# H0FR70.net
KiCad netlist of a schematic drawn in EAGLE
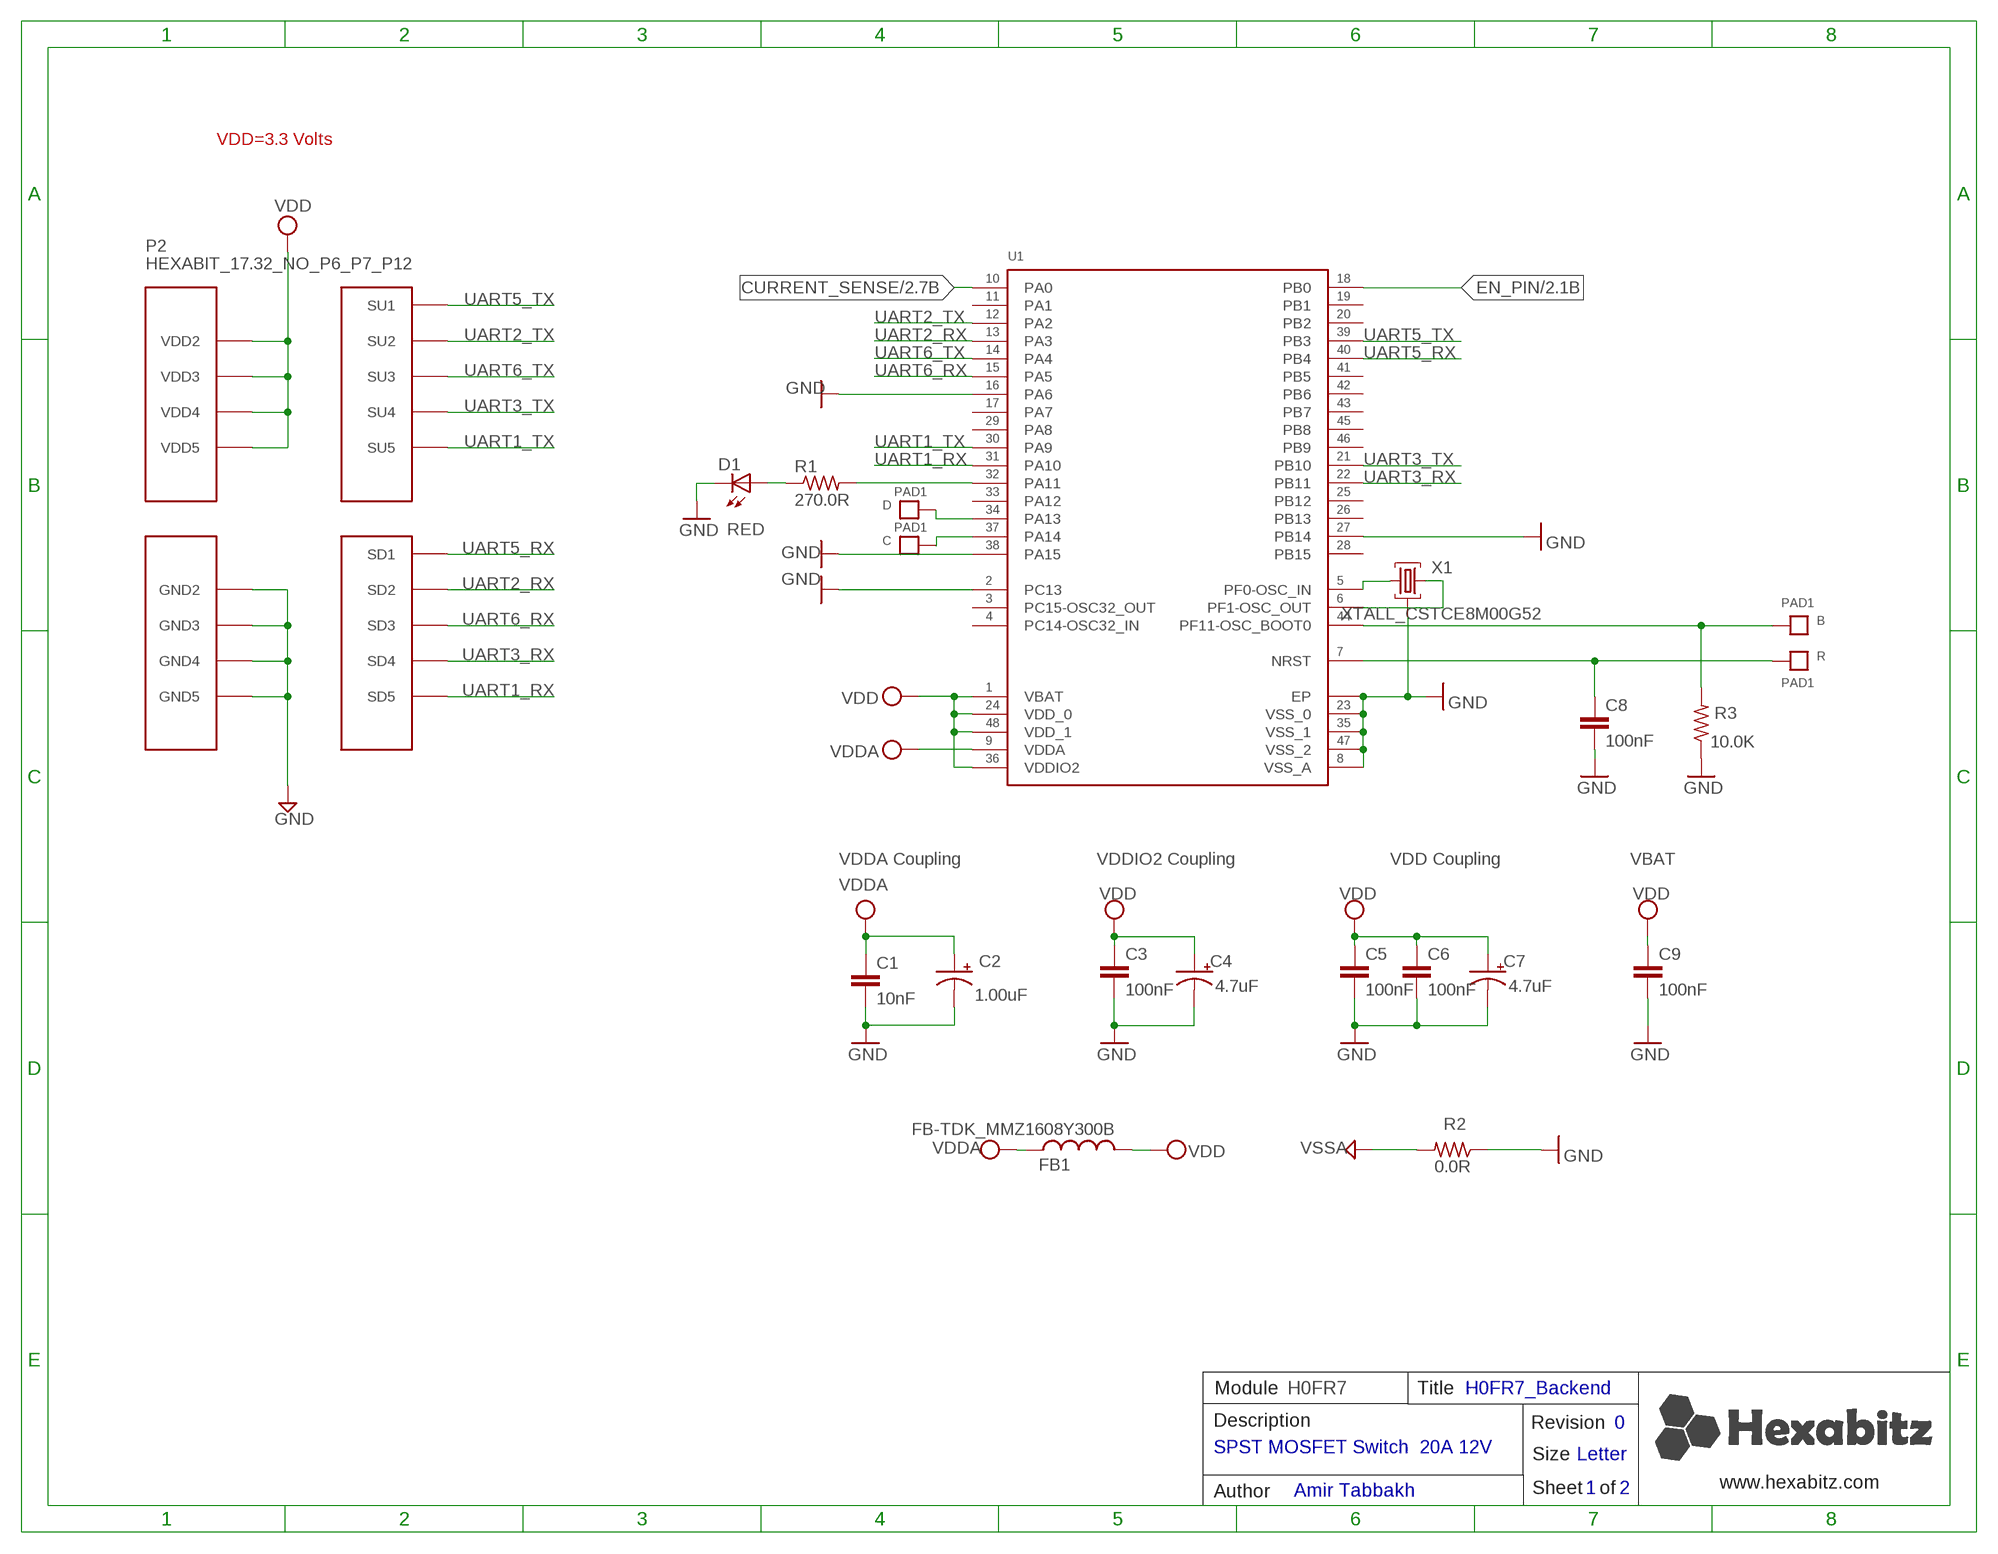
[diagram p0: schematic, sheet 1]
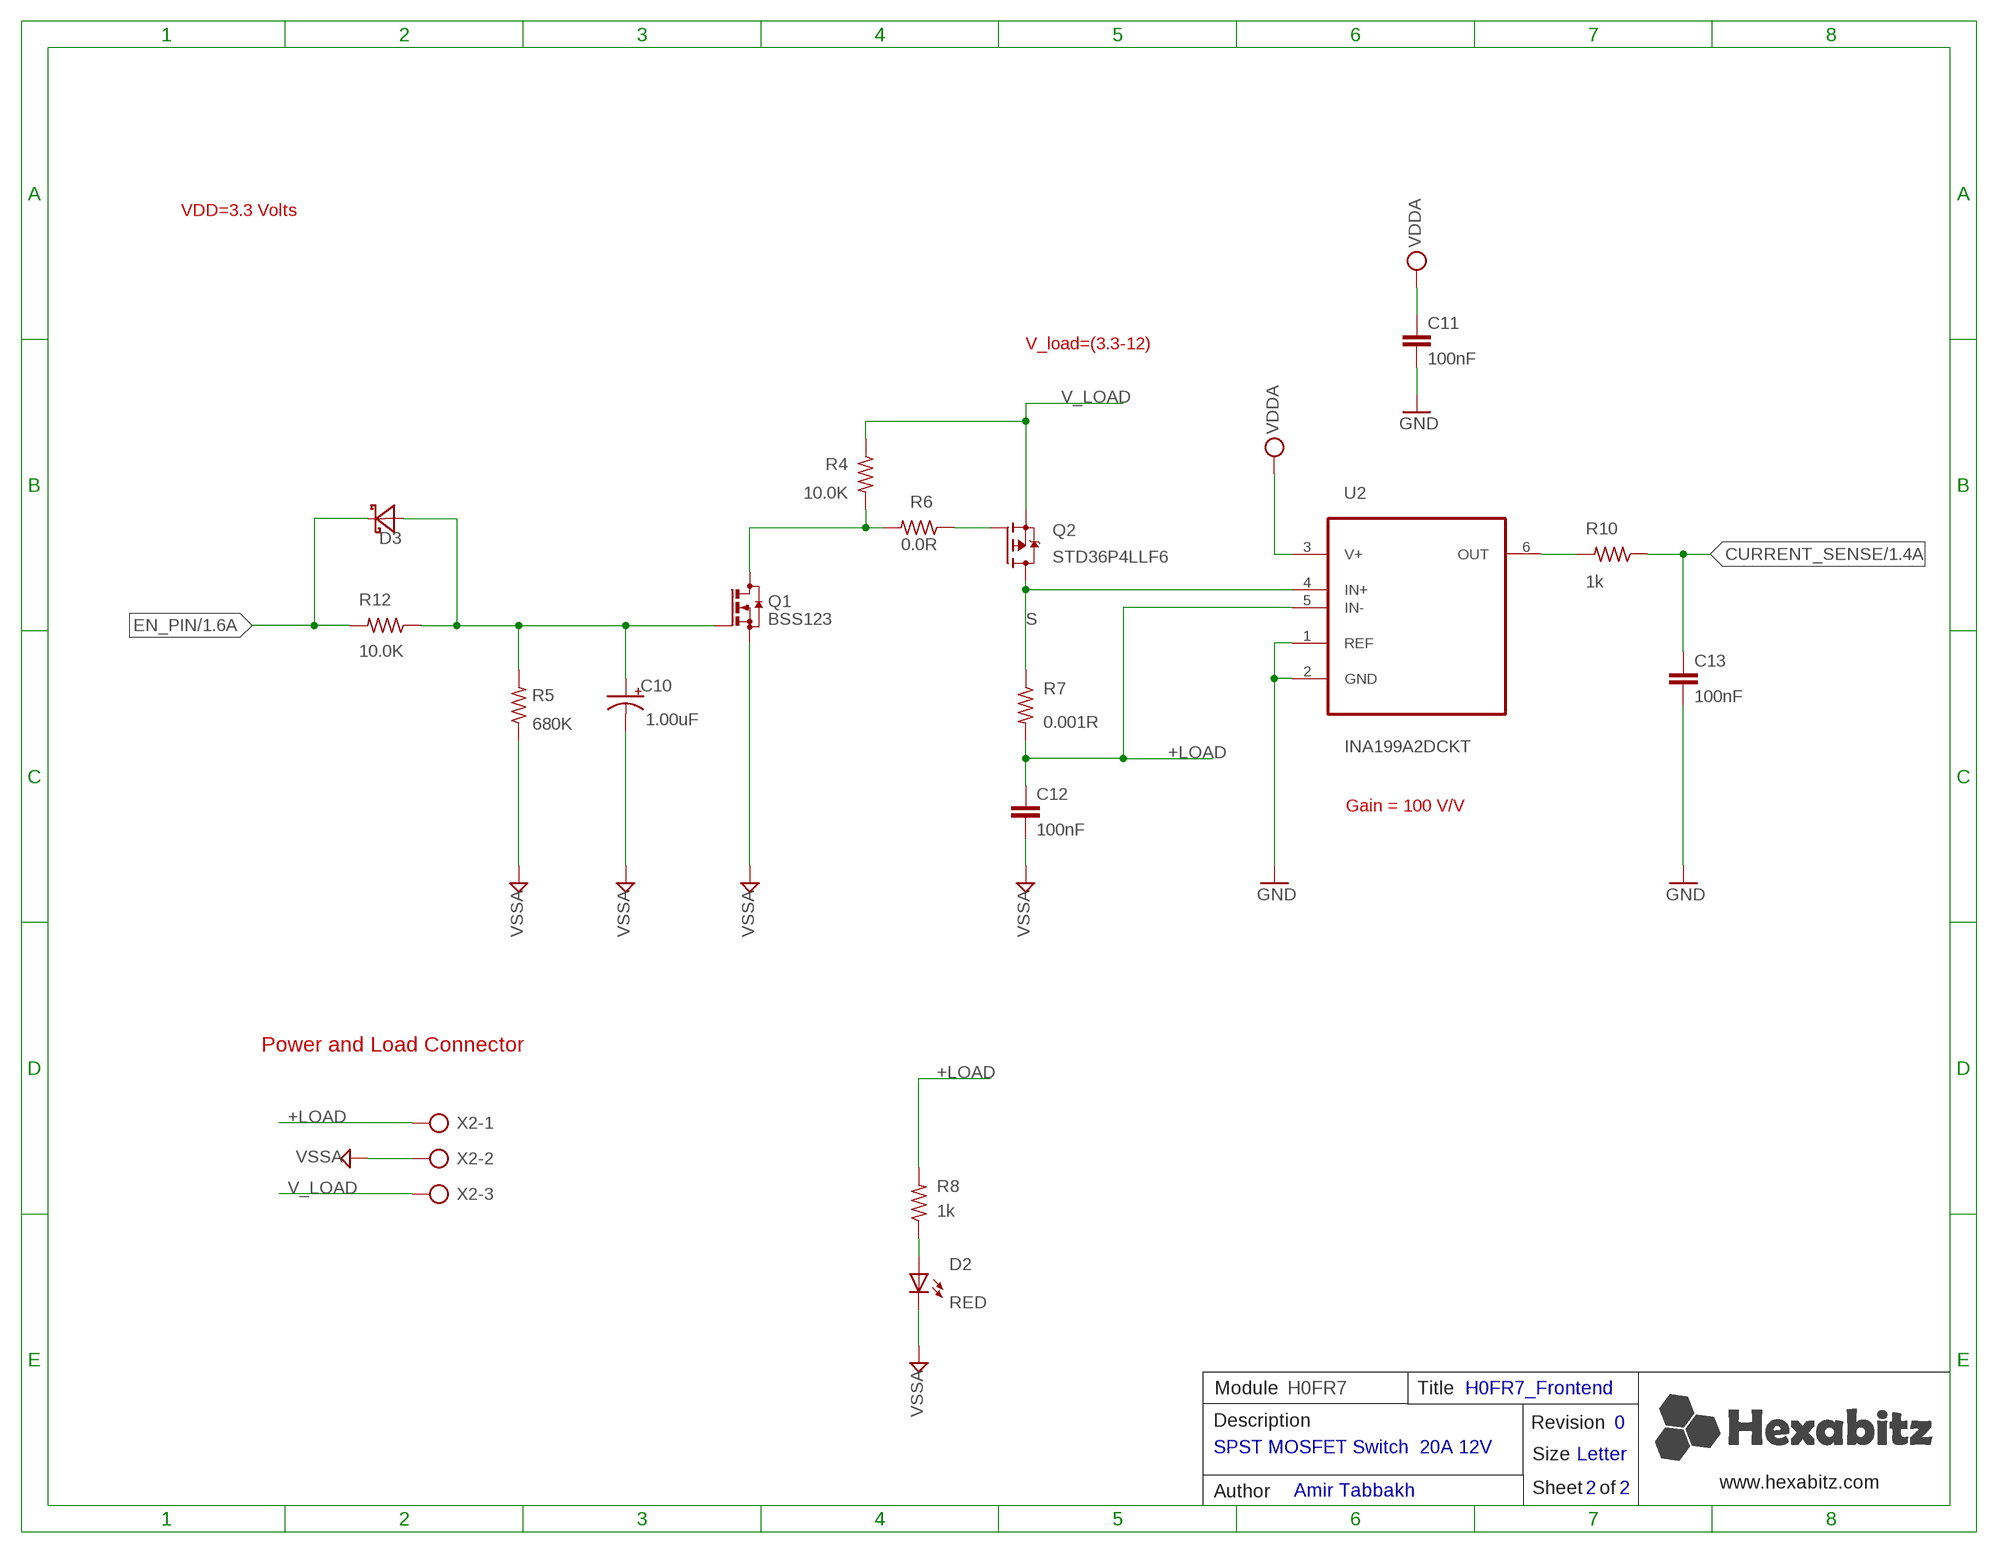
[diagram p1: schematic, sheet 2]

(export (version "E")
  (design (tool "Eeschema 10.0.6"))
  (components
    (comp (ref "B")
      (value "PAD1")
      (footprint "eagle-import:PAD1")
      (libsource (lib "eagle-import") (part "PAD1"))
    )
    (comp (ref "C")
      (value "PAD1")
      (footprint "eagle-import:PAD1")
      (libsource (lib "eagle-import") (part "PAD1"))
    )
    (comp (ref "C1")
      (value "10nF")
      (footprint "eagle-import:C-0603")
      (fields
        (field (name "CAPACITANCE") "10nF")
        (field (name "MFN") "KEMET")
        (field (name "MPN") "C0603C103K5RACTU")
        (field (name "OCTOPART_URL") "https://octopart.com/c0603c103k5ractu-kemet-133094?r=sp&s=R_iPBxLnSmGqhkU2rIMFpg")
        (field (name "TOLERANCE") "10%")
        (field (name "VOLTAGE_RATING") "50V")
      )
      (libsource (lib "eagle-import") (part "C-0603"))
    )
    (comp (ref "C2")
      (value "1.00uF")
      (footprint "eagle-import:C-0805-POL")
      (fields
        (field (name "CAPACITANCE") "1.00uF")
        (field (name "MFN") "Yageo")
        (field (name "MPN") "CC0805KKX7R7BB105")
        (field (name "OCTOPART_URL") "https://octopart.com/cc0805kkx7r7bb105-yageo-8376555?r=sp&s=YKl1wwtkROau_X5nniH2ig")
        (field (name "TOLERANCE") "10%")
        (field (name "VOLTAGE_RATING") "16V")
      )
      (libsource (lib "eagle-import") (part "C-0805-POL"))
    )
    (comp (ref "C3")
      (value "100nF")
      (footprint "eagle-import:C-0603")
      (fields
        (field (name "CAPACITANCE") "100nF")
        (field (name "MFN") "KEMET")
        (field (name "MPN") "C0603C104K8RACTU")
        (field (name "OCTOPART_URL") "https://octopart.com/c0603c104k8ractu-kemet-145075?r=sp&s=9bS9ASSwSEqMCE9KBEQZ0g")
        (field (name "TOLERANCE") "10%")
        (field (name "VOLTAGE_RATING") "10V")
      )
      (libsource (lib "eagle-import") (part "C-0603"))
    )
    (comp (ref "C4")
      (value "4.7uF")
      (footprint "eagle-import:C-0805-POL")
      (fields
        (field (name "CAPACITANCE") "4.7uF")
        (field (name "MFN") "Murata")
        (field (name "MPN") "GRM21BC81E475KA12L")
        (field (name "OCTOPART_URL") "https://octopart.com/grm21bc81e475ka12l-murata-10331911?r=sp&s=RY3qZSD8T6mG6TC9CHI5qQ")
        (field (name "TOLERANCE") "10%")
        (field (name "VOLTAGE_RATING") "25V")
      )
      (libsource (lib "eagle-import") (part "C-0805-POL"))
    )
    (comp (ref "C5")
      (value "100nF")
      (footprint "eagle-import:C-0603")
      (fields
        (field (name "CAPACITANCE") "100nF")
        (field (name "MFN") "KEMET")
        (field (name "MPN") "C0603C104K8RACTU")
        (field (name "OCTOPART_URL") "https://octopart.com/c0603c104k8ractu-kemet-145075?r=sp&s=9bS9ASSwSEqMCE9KBEQZ0g")
        (field (name "TOLERANCE") "10%")
        (field (name "VOLTAGE_RATING") "10")
      )
      (libsource (lib "eagle-import") (part "C-0603"))
    )
    (comp (ref "C6")
      (value "100nF")
      (footprint "eagle-import:C-0603")
      (fields
        (field (name "CAPACITANCE") "100nF")
        (field (name "MFN") "KEMET")
        (field (name "MPN") "C0603C104K8RACTU")
        (field (name "OCTOPART_URL") "https://octopart.com/c0603c104k8ractu-kemet-145075?r=sp&s=9bS9ASSwSEqMCE9KBEQZ0g")
        (field (name "TOLERANCE") "10%")
        (field (name "VOLTAGE_RATING") "10V")
      )
      (libsource (lib "eagle-import") (part "C-0603"))
    )
    (comp (ref "C7")
      (value "4.7uF")
      (footprint "eagle-import:C-0805-POL")
      (fields
        (field (name "CAPACITANCE") "4.7uF")
        (field (name "MFN") "Murata")
        (field (name "MPN") "GRM21BC81E475KA12L")
        (field (name "OCTOPART_URL") "https://octopart.com/grm21bc81e475ka12l-murata-10331911?r=sp&s=RY3qZSD8T6mG6TC9CHI5qQ")
        (field (name "TOLERANCE") "10%")
        (field (name "VOLTAGE_RATING") "25V")
      )
      (libsource (lib "eagle-import") (part "C-0805-POL"))
    )
    (comp (ref "C8")
      (value "100nF")
      (footprint "eagle-import:C-0603")
      (fields
        (field (name "CAPACITANCE") "100nF")
        (field (name "MFN") "KEMET")
        (field (name "MPN") "C0603C104K8RACTU")
        (field (name "OCTOPART_URL") "https://octopart.com/c0603c104k8ractu-kemet-145075?r=sp&s=9bS9ASSwSEqMCE9KBEQZ0g")
        (field (name "TOLERANCE") "10%")
        (field (name "VOLTAGE_RATING") "10V")
      )
      (libsource (lib "eagle-import") (part "C-0603"))
    )
    (comp (ref "C9")
      (value "100nF")
      (footprint "eagle-import:C-0603")
      (fields
        (field (name "CAPACITANCE") "100nF")
        (field (name "MFN") "KEMET")
        (field (name "MPN") "C0603C104K8RACTU")
        (field (name "OCTOPART_URL") "https://octopart.com/c0603c104k8ractu-kemet-145075?r=sp&s=9bS9ASSwSEqMCE9KBEQZ0g")
        (field (name "TOLERANCE") "10V")
        (field (name "VOLTAGE_RATING") "10%")
      )
      (libsource (lib "eagle-import") (part "C-0603"))
    )
    (comp (ref "D")
      (value "PAD1")
      (footprint "eagle-import:PAD1")
      (libsource (lib "eagle-import") (part "PAD1"))
    )
    (comp (ref "D1")
      (value "RED")
      (footprint "eagle-import:VLMS1300-GS08")
      (fields
        (field (name "MPN") "VLMS1300-GS08")
        (field (name "MFN") "Vishay")
        (field (name "MPN_1") "VLMS1300-GS08")
        (field (name "OCTOPART_URL") "https://octopart.com/vlms1300-gs08-vishay-21709201?r=sp&s=_gcP4_q8T1SC6PJQPTQ9yA")
      )
      (libsource (lib "eagle-import") (part "VLMS1300-GS08"))
    )
    (comp (ref "FB1")
      (value "FB-TDK_MMZ1608Y300B")
      (footprint "eagle-import:FB-TDK_MMZ1608Y300B")
      (fields
        (field (name "MFN") "TDK ")
        (field (name "MPN") "MMZ1608Y300B")
        (field (name "OCTOPART_URL") "https://octopart.com/mmz1608y300b-tdk-368280?r=sp&s=cd9_2ZEqQ9q9UNBuQgHAiA")
      )
      (libsource (lib "eagle-import") (part "FB-TDK_MMZ1608Y300B"))
    )
    (comp (ref "P2")
      (value "HEXABIT_17.32_NO_P6_P7_P12")
      (footprint "eagle-import:HEXABIT_17.32_NO_P6_P7_P12")
      (libsource (lib "eagle-import") (part "HEXABIT_?_NO_P6_P7_P1217.32"))
    )
    (comp (ref "R")
      (value "PAD1")
      (footprint "eagle-import:PAD1")
      (libsource (lib "eagle-import") (part "PAD1"))
    )
    (comp (ref "R1")
      (value "270.0R")
      (footprint "eagle-import:R-0603")
      (fields
        (field (name "MFN") "Yageo")
        (field (name "MPN") "RC0603FR-07270RL")
        (field (name "OCTOPART_URL") "https://octopart.com/search?q=RC0603FR-07270RL&start=0")
        (field (name "RESISTANCE") "270.0 Ohm")
        (field (name "TOLERANCE") "1%")
      )
      (libsource (lib "eagle-import") (part "R-0603"))
    )
    (comp (ref "R2")
      (value "0.0R")
      (footprint "eagle-import:R-0603")
      (fields
        (field (name "MFN") "Yageo")
        (field (name "MPN") "RC0603JR-070RL")
        (field (name "OCTOPART_URL") "https://octopart.com/rc0603jr-070rl-yageo-1241539?r=sp&s=X2NteqRjRNWrnx42Y0aliA")
        (field (name "RESISTANCE") "0.0 Ohm")
      )
      (libsource (lib "eagle-import") (part "R-0603"))
    )
    (comp (ref "R3")
      (value "10.0K")
      (footprint "eagle-import:R-0603")
      (fields
        (field (name "MFN") "Yageo")
        (field (name "MPN") "RC0603JR-0710KL")
        (field (name "OCTOPART_URL") "https://octopart.com/search?q=RC0603JR-0710KL&start=0")
        (field (name "RESISTANCE") "10.0K Ohm")
        (field (name "TOLERANCE") "5%")
      )
      (libsource (lib "eagle-import") (part "R-0603"))
    )
    (comp (ref "U1")
      (value "STM32F091CBU6")
      (footprint "eagle-import:STM32F091CBU6")
      (libsource (lib "eagle-import") (part "STM32F091CBU6"))
    )
    (comp (ref "X1")
      (value "XTALL_CSTCE8M00G52")
      (footprint "eagle-import:XTALL_CSTCE8M00G52")
      (fields (field (name "MPN") "CSTCE8M00G52Z-R0"))
      (libsource (lib "eagle-import") (part "XTALL_CSTCE8M00G52"))
    )
    (comp (ref "C10")
      (value "1.00uF")
      (footprint "eagle-import:C-0805-POL")
      (fields
        (field (name "CAPACITANCE") "1.00uF")
        (field (name "MFN") "Yageo")
        (field (name "MPN") "CC0805KKX7R7BB105")
        (field (name "OCTOPART_URL") "https://octopart.com/cc0805kkx7r7bb105-yageo-8376555?r=sp&s=YKl1wwtkROau_X5nniH2ig")
        (field (name "TOLERANCE") "10%")
        (field (name "VOLTAGE_RATING") "16V")
      )
      (libsource (lib "eagle-import") (part "C-0805-POL"))
    )
    (comp (ref "C11")
      (value "100nF")
      (footprint "eagle-import:C-0603")
      (fields
        (field (name "CAPACITANCE") "100nF")
        (field (name "MFN") "KEMET")
        (field (name "MPN") "C0603C104K8RACTU")
        (field (name "OCTOPART_URL") "https://octopart.com/c0603c104k8ractu-kemet-145075?r=sp&s=9bS9ASSwSEqMCE9KBEQZ0g")
        (field (name "TOLERANCE") "10V")
        (field (name "VOLTAGE_RATING") "10%")
      )
      (libsource (lib "eagle-import") (part "C-0603"))
    )
    (comp (ref "C12")
      (value "100nF")
      (footprint "eagle-import:C-0603")
      (fields
        (field (name "CAPACITANCE") "100nF")
        (field (name "MFN") "KEMET")
        (field (name "MPN") "C0603C104K8RACTU")
        (field (name "OCTOPART_URL") "https://octopart.com/c0603c104k8ractu-kemet-145075?r=sp&s=9bS9ASSwSEqMCE9KBEQZ0g")
        (field (name "TOLERANCE") "10%")
        (field (name "VOLTAGE_RATING") "10V")
      )
      (libsource (lib "eagle-import") (part "C-0603"))
    )
    (comp (ref "C13")
      (value "100nF")
      (footprint "eagle-import:C-0603")
      (fields
        (field (name "CAPACITANCE") "100nF")
        (field (name "MFN") "KEMET")
        (field (name "MPN") "C0603C104K8RACTU")
        (field (name "OCTOPART_URL") "https://octopart.com/c0603c104k8ractu-kemet-145075?r=sp&s=9bS9ASSwSEqMCE9KBEQZ0g")
        (field (name "TOLERANCE") "10%")
        (field (name "VOLTAGE_RATING") "10V")
      )
      (libsource (lib "eagle-import") (part "C-0603"))
    )
    (comp (ref "D2")
      (value "RED")
      (footprint "eagle-import:VLMS1300-GS08")
      (fields
        (field (name "MPN") "VLMS1300-GS08")
        (field (name "MFN") "Vishay")
        (field (name "MPN_1") "VLMO1300-GS08 ")
        (field (name "OCTOPART_URL") "https://octopart.com/vlmo1300-gs08-vishay-21709200?r=sp#")
      )
      (libsource (lib "eagle-import") (part "VLMS1300-GS08"))
    )
    (comp (ref "D3")
      (value "SMD-DIODE-SCHOTTKY-40V-300MA(SOD-323)")
      (footprint "eagle-import:SOD-323")
      (fields (field (name "MF") "STMicroelectronics") (field (name "MP") "BAT54JFILM"))
      (libsource (lib "eagle-import") (part "SMD-DIODE-SCHOTTKY-40V-300MA(SOD-323)"))
    )
    (comp (ref "Q1")
      (value "BSS123")
      (footprint "eagle-import:SOT23")
      (libsource (lib "eagle-import") (part "BSS123"))
    )
    (comp (ref "Q2")
      (value "STD36P4LLF6")
      (footprint "eagle-import:DPAK-3")
      (libsource (lib "eagle-import") (part "STD36P4LLF6"))
    )
    (comp (ref "R4")
      (value "10.0K")
      (footprint "eagle-import:R-0603")
      (fields
        (field (name "MFN") "Yageo")
        (field (name "MPN") "RC0603JR-0710KL")
        (field (name "OCTOPART_URL") "https://octopart.com/search?q=RC0603JR-0710KL&start=0")
        (field (name "RESISTANCE") "10.0K Ohm")
        (field (name "TOLERANCE") "5%")
      )
      (libsource (lib "eagle-import") (part "R-0603"))
    )
    (comp (ref "R5")
      (value "680K")
      (footprint "eagle-import:R-0603")
      (fields
        (field (name "MFN") "Yageo")
        (field (name "MPN") "RC0603JR-07680KL")
        (field (name "OCTOPART_URL") "https://octopart.com/rc0603jr-07680kl-yageo-40953169?r=sp")
        (field (name "RESISTANCE") "680K Ohm")
        (field (name "TOLERANCE") "5%")
      )
      (libsource (lib "eagle-import") (part "R-0603"))
    )
    (comp (ref "R6")
      (value "0.0R")
      (footprint "eagle-import:R-0603")
      (fields
        (field (name "MFN") "Yageo")
        (field (name "MPN") "RC0603JR-070RL")
        (field (name "OCTOPART_URL") "https://octopart.com/rc0603jr-070rl-yageo-1241539?r=sp&s=X2NteqRjRNWrnx42Y0aliA")
        (field (name "RESISTANCE") "0.0 Ohm")
      )
      (libsource (lib "eagle-import") (part "R-0603"))
    )
    (comp (ref "R7")
      (value "0.001R")
      (footprint "eagle-import:R2512")
      (libsource (lib "eagle-import") (part "R-US_R2512"))
    )
    (comp (ref "R8")
      (value "1k")
      (footprint "eagle-import:R-0603")
      (fields
        (field (name "MFN") "Yageo")
        (field (name "MPN") "RC0603JR-071KL")
        (field (name "OCTOPART_URL") "https://octopart.com/rc0603jr-071kl-yageo-55402888?r=sp")
        (field (name "RESISTANCE") "1k")
        (field (name "TOLERANCE") "1%")
      )
      (libsource (lib "eagle-import") (part "R-0603"))
    )
    (comp (ref "R10")
      (value "1k")
      (footprint "eagle-import:R-0603")
      (fields
        (field (name "MFN") "Yageo")
        (field (name "MPN") "RC0603JR-071KL")
        (field (name "OCTOPART_URL") "https://octopart.com/rc0603jr-071kl-yageo-55402888?r=sp")
        (field (name "RESISTANCE") "1k")
        (field (name "TOLERANCE") "5%")
      )
      (libsource (lib "eagle-import") (part "R-0603"))
    )
    (comp (ref "R12")
      (value "10.0K")
      (footprint "eagle-import:R-0603")
      (fields
        (field (name "MFN") "Yageo")
        (field (name "MPN") "RC0603JR-0710KL")
        (field (name "OCTOPART_URL") "https://octopart.com/search?q=RC0603JR-0710KL&start=0")
        (field (name "RESISTANCE") "10.0K Ohm")
        (field (name "TOLERANCE") "5%")
      )
      (libsource (lib "eagle-import") (part "R-0603"))
    )
    (comp (ref "U2")
      (value "INA199A2DCKT")
      (footprint "eagle-import:SOT65P210X110-6N")
      (libsource (lib "eagle-import") (part "INA199A2DCKT"))
    )
    (comp (ref "X2")
      (value "AK500/3")
      (footprint "eagle-import:AK500_3")
      (libsource (lib "eagle-import") (part "AK500/3"))
    )
  )
  (nets
    (net (code "1") (name "+LOAD") (class "Default")
      (node (ref "C12") (pin "1") (pinfunction "1_1") (pintype "passive"))
      (node (ref "R7") (pin "2") (pinfunction "2_2") (pintype "passive"))
      (node (ref "R8") (pin "2") (pinfunction "2_2") (pintype "passive"))
      (node (ref "U2") (pin "5") (pinfunction "IN-_5") (pintype "input"))
      (node (ref "X2") (pin "1") (pinfunction "KL_1") (pintype "passive"))
    )
    (net (code "2") (name "AGND") (class "Default")
      (node (ref "C10") (pin "2") (pinfunction "-_2") (pintype "passive"))
      (node (ref "C12") (pin "2") (pinfunction "2_2") (pintype "passive"))
      (node (ref "D2") (pin "C") (pinfunction "C_C") (pintype "passive"))
      (node (ref "Q1") (pin "2") (pinfunction "S_2") (pintype "passive"))
      (node (ref "R2") (pin "2") (pinfunction "2_2") (pintype "passive"))
      (node (ref "R5") (pin "1") (pinfunction "1_1") (pintype "passive"))
      (node (ref "X2") (pin "2") (pinfunction "KL_2") (pintype "passive"))
    )
    (net (code "3") (name "CURRENT_SENSE") (class "Default")
      (node (ref "C13") (pin "1") (pinfunction "1_1") (pintype "passive"))
      (node (ref "R10") (pin "1") (pinfunction "1_1") (pintype "passive"))
      (node (ref "U1") (pin "P$10") (pinfunction "PA0_P$10") (pintype "bidirectional"))
    )
    (net (code "4") (name "EN_PIN") (class "Default")
      (node (ref "D3") (pin "-") (pinfunction "C_-") (pintype "passive"))
      (node (ref "R12") (pin "2") (pinfunction "2_2") (pintype "passive"))
      (node (ref "U1") (pin "P$18") (pinfunction "PB0_P$18") (pintype "bidirectional"))
    )
    (net (code "5") (name "GND") (class "Default")
      (node (ref "C1") (pin "2") (pinfunction "2_2") (pintype "passive"))
      (node (ref "C11") (pin "2") (pinfunction "2_2") (pintype "passive"))
      (node (ref "C13") (pin "2") (pinfunction "2_2") (pintype "passive"))
      (node (ref "C2") (pin "2") (pinfunction "-_2") (pintype "passive"))
      (node (ref "C3") (pin "2") (pinfunction "2_2") (pintype "passive"))
      (node (ref "C4") (pin "2") (pinfunction "-_2") (pintype "passive"))
      (node (ref "C5") (pin "2") (pinfunction "2_2") (pintype "passive"))
      (node (ref "C6") (pin "2") (pinfunction "2_2") (pintype "passive"))
      (node (ref "C7") (pin "2") (pinfunction "-_2") (pintype "passive"))
      (node (ref "C8") (pin "2") (pinfunction "2_2") (pintype "passive"))
      (node (ref "C9") (pin "2") (pinfunction "2_2") (pintype "passive"))
      (node (ref "D1") (pin "C") (pinfunction "C_C") (pintype "passive"))
      (node (ref "P2") (pin "PAD_PD10") (pinfunction "GND4_PAD_PD10") (pintype "power_in"))
      (node (ref "P2") (pin "PAD_PD11") (pinfunction "GND5_PAD_PD11") (pintype "power_in"))
      (node (ref "P2") (pin "PAD_PD8") (pinfunction "GND2_PAD_PD8") (pintype "power_in"))
      (node (ref "P2") (pin "PAD_PD9") (pinfunction "GND3_PAD_PD9") (pintype "power_in"))
      (node (ref "R2") (pin "1") (pinfunction "1_1") (pintype "passive"))
      (node (ref "R3") (pin "1") (pinfunction "1_1") (pintype "passive"))
      (node (ref "U1") (pin "EP") (pinfunction "EP_EP") (pintype "power_in"))
      (node (ref "U1") (pin "P$16") (pinfunction "PA6_P$16") (pintype "bidirectional"))
      (node (ref "U1") (pin "P$2") (pinfunction "PC13_P$2") (pintype "bidirectional"))
      (node (ref "U1") (pin "P$23") (pinfunction "VSS_0_P$23") (pintype "power_in"))
      (node (ref "U1") (pin "P$27") (pinfunction "PB14_P$27") (pintype "bidirectional"))
      (node (ref "U1") (pin "P$35") (pinfunction "VSS_1_P$35") (pintype "power_in"))
      (node (ref "U1") (pin "P$38") (pinfunction "PA15_P$38") (pintype "bidirectional"))
      (node (ref "U1") (pin "P$47") (pinfunction "VSS_2_P$47") (pintype "power_in"))
      (node (ref "U1") (pin "P$8") (pinfunction "VSS_A_P$8") (pintype "power_in"))
      (node (ref "U2") (pin "1") (pinfunction "REF_1") (pintype "input"))
      (node (ref "U2") (pin "2") (pinfunction "GND_2") (pintype "passive"))
      (node (ref "X1") (pin "P$2") (pinfunction "2_P$2") (pintype "passive"))
    )
    (net (code "6") (name "Net-(C10-+)") (class "Default")
      (node (ref "C10") (pin "1") (pinfunction "+_1") (pintype "passive"))
      (node (ref "D3") (pin "+") (pinfunction "A_+") (pintype "passive"))
      (node (ref "Q1") (pin "1") (pinfunction "G_1") (pintype "passive"))
      (node (ref "R12") (pin "1") (pinfunction "1_1") (pintype "passive"))
      (node (ref "R5") (pin "2") (pinfunction "2_2") (pintype "passive"))
    )
    (net (code "7") (name "Net-(D1-PadA)") (class "Default")
      (node (ref "D1") (pin "A") (pinfunction "A_A") (pintype "passive"))
      (node (ref "R1") (pin "1") (pinfunction "1_1") (pintype "passive"))
    )
    (net (code "8") (name "Net-(D2-PadA)") (class "Default")
      (node (ref "D2") (pin "A") (pinfunction "A_A") (pintype "passive"))
      (node (ref "R8") (pin "1") (pinfunction "1_1") (pintype "passive"))
    )
    (net (code "9") (name "Net-(Q1-D)") (class "Default")
      (node (ref "Q1") (pin "3") (pinfunction "D_3") (pintype "passive"))
      (node (ref "R4") (pin "2") (pinfunction "2_2") (pintype "passive"))
      (node (ref "R6") (pin "2") (pinfunction "2_2") (pintype "passive"))
    )
    (net (code "10") (name "Net-(Q2-G)") (class "Default")
      (node (ref "Q2") (pin "1") (pinfunction "G_1") (pintype "passive"))
      (node (ref "R6") (pin "1") (pinfunction "1_1") (pintype "passive"))
    )
    (net (code "11") (name "Net-(U1-NRST)") (class "Default")
      (node (ref "C8") (pin "1") (pinfunction "1_1") (pintype "passive"))
      (node (ref "R") (pin "P$1") (pinfunction "P$1_P$1") (pintype "passive"))
      (node (ref "R") (pin "P$2") (pinfunction "P$1_P$2") (pintype "passive"))
      (node (ref "U1") (pin "P$7") (pinfunction "NRST_P$7") (pintype "passive"))
    )
    (net (code "12") (name "Net-(U1-PA11)") (class "Default")
      (node (ref "R1") (pin "2") (pinfunction "2_2") (pintype "passive"))
      (node (ref "U1") (pin "P$32") (pinfunction "PA11_P$32") (pintype "bidirectional"))
    )
    (net (code "13") (name "Net-(U1-PA13)") (class "Default")
      (node (ref "D") (pin "P$1") (pinfunction "P$1_P$1") (pintype "passive"))
      (node (ref "D") (pin "P$2") (pinfunction "P$1_P$2") (pintype "passive"))
      (node (ref "U1") (pin "P$34") (pinfunction "PA13_P$34") (pintype "bidirectional"))
    )
    (net (code "14") (name "Net-(U1-PA14)") (class "Default")
      (node (ref "C") (pin "P$1") (pinfunction "P$1_P$1") (pintype "passive"))
      (node (ref "C") (pin "P$2") (pinfunction "P$1_P$2") (pintype "passive"))
      (node (ref "U1") (pin "P$37") (pinfunction "PA14_P$37") (pintype "bidirectional"))
    )
    (net (code "15") (name "Net-(U1-PF0-OSC_IN)") (class "Default")
      (node (ref "U1") (pin "P$5") (pinfunction "PF0-OSC_IN_P$5") (pintype "bidirectional"))
      (node (ref "X1") (pin "P$1") (pinfunction "1_P$1") (pintype "passive"))
    )
    (net (code "16") (name "Net-(U1-PF1-OSC_OUT)") (class "Default")
      (node (ref "U1") (pin "P$6") (pinfunction "PF1-OSC_OUT_P$6") (pintype "bidirectional"))
      (node (ref "X1") (pin "P$3") (pinfunction "3_P$3") (pintype "passive"))
    )
    (net (code "17") (name "Net-(U1-PF11-OSC_BOOT0)") (class "Default")
      (node (ref "B") (pin "P$1") (pinfunction "P$1_P$1") (pintype "passive"))
      (node (ref "B") (pin "P$2") (pinfunction "P$1_P$2") (pintype "passive"))
      (node (ref "R3") (pin "2") (pinfunction "2_2") (pintype "passive"))
      (node (ref "U1") (pin "P$44") (pinfunction "PF11-OSC_BOOT0_P$44") (pintype "bidirectional"))
    )
    (net (code "18") (name "Net-(U2-OUT)") (class "Default")
      (node (ref "R10") (pin "2") (pinfunction "2_2") (pintype "passive"))
      (node (ref "U2") (pin "6") (pinfunction "OUT_6") (pintype "output"))
    )
    (net (code "19") (name "S") (class "Default")
      (node (ref "Q2") (pin "4") (pinfunction "D_4") (pintype "passive"))
      (node (ref "R7") (pin "1") (pinfunction "1_1") (pintype "passive"))
      (node (ref "U2") (pin "4") (pinfunction "IN+_4") (pintype "input"))
    )
    (net (code "20") (name "UART1_RX") (class "Default")
      (node (ref "P2") (pin "PAD_PD5") (pinfunction "SD5_PAD_PD5") (pintype "bidirectional"))
      (node (ref "U1") (pin "P$31") (pinfunction "PA10_P$31") (pintype "bidirectional"))
    )
    (net (code "21") (name "UART1_TX") (class "Default")
      (node (ref "P2") (pin "PAD_PU5") (pinfunction "SU5_PAD_PU5") (pintype "bidirectional"))
      (node (ref "U1") (pin "P$30") (pinfunction "PA9_P$30") (pintype "bidirectional"))
    )
    (net (code "22") (name "UART2_RX") (class "Default")
      (node (ref "P2") (pin "PAD_PD2") (pinfunction "SD2_PAD_PD2") (pintype "bidirectional"))
      (node (ref "U1") (pin "P$13") (pinfunction "PA3_P$13") (pintype "bidirectional"))
    )
    (net (code "23") (name "UART2_TX") (class "Default")
      (node (ref "P2") (pin "PAD_PU2") (pinfunction "SU2_PAD_PU2") (pintype "bidirectional"))
      (node (ref "U1") (pin "P$12") (pinfunction "PA2_P$12") (pintype "bidirectional"))
    )
    (net (code "24") (name "UART3_RX") (class "Default")
      (node (ref "P2") (pin "PAD_PD4") (pinfunction "SD4_PAD_PD4") (pintype "bidirectional"))
      (node (ref "U1") (pin "P$22") (pinfunction "PB11_P$22") (pintype "bidirectional"))
    )
    (net (code "25") (name "UART3_TX") (class "Default")
      (node (ref "P2") (pin "PAD_PU4") (pinfunction "SU4_PAD_PU4") (pintype "bidirectional"))
      (node (ref "U1") (pin "P$21") (pinfunction "PB10_P$21") (pintype "bidirectional"))
    )
    (net (code "26") (name "UART5_RX") (class "Default")
      (node (ref "P2") (pin "PAD_PD1") (pinfunction "SD1_PAD_PD1") (pintype "bidirectional"))
      (node (ref "U1") (pin "P$40") (pinfunction "PB4_P$40") (pintype "bidirectional"))
    )
    (net (code "27") (name "UART5_TX") (class "Default")
      (node (ref "P2") (pin "PAD_PU1") (pinfunction "SU1_PAD_PU1") (pintype "bidirectional"))
      (node (ref "U1") (pin "P$39") (pinfunction "PB3_P$39") (pintype "bidirectional"))
    )
    (net (code "28") (name "UART6_RX") (class "Default")
      (node (ref "P2") (pin "PAD_PD3") (pinfunction "SD3_PAD_PD3") (pintype "bidirectional"))
      (node (ref "U1") (pin "P$15") (pinfunction "PA5_P$15") (pintype "bidirectional"))
    )
    (net (code "29") (name "UART6_TX") (class "Default")
      (node (ref "P2") (pin "PAD_PU3") (pinfunction "SU3_PAD_PU3") (pintype "bidirectional"))
      (node (ref "U1") (pin "P$14") (pinfunction "PA4_P$14") (pintype "bidirectional"))
    )
    (net (code "30") (name "VDD") (class "Default")
      (node (ref "C3") (pin "1") (pinfunction "1_1") (pintype "passive"))
      (node (ref "C4") (pin "1") (pinfunction "+_1") (pintype "passive"))
      (node (ref "C5") (pin "1") (pinfunction "1_1") (pintype "passive"))
      (node (ref "C6") (pin "1") (pinfunction "1_1") (pintype "passive"))
      (node (ref "C7") (pin "1") (pinfunction "+_1") (pintype "passive"))
      (node (ref "C9") (pin "1") (pinfunction "1_1") (pintype "passive"))
      (node (ref "FB1") (pin "2") (pinfunction "2_2") (pintype "passive"))
      (node (ref "P2") (pin "PAD_PU10") (pinfunction "VDD4_PAD_PU10") (pintype "power_in"))
      (node (ref "P2") (pin "PAD_PU11") (pinfunction "VDD5_PAD_PU11") (pintype "power_in"))
      (node (ref "P2") (pin "PAD_PU8") (pinfunction "VDD2_PAD_PU8") (pintype "power_in"))
      (node (ref "P2") (pin "PAD_PU9") (pinfunction "VDD3_PAD_PU9") (pintype "power_in"))
      (node (ref "U1") (pin "P$1") (pinfunction "VBAT_P$1") (pintype "power_in"))
      (node (ref "U1") (pin "P$24") (pinfunction "VDD_0_P$24") (pintype "power_in"))
      (node (ref "U1") (pin "P$36") (pinfunction "VDDIO2_P$36") (pintype "power_in"))
      (node (ref "U1") (pin "P$48") (pinfunction "VDD_1_P$48") (pintype "power_in"))
    )
    (net (code "31") (name "VDDA") (class "Default")
      (node (ref "C1") (pin "1") (pinfunction "1_1") (pintype "passive"))
      (node (ref "C11") (pin "1") (pinfunction "1_1") (pintype "passive"))
      (node (ref "C2") (pin "1") (pinfunction "+_1") (pintype "passive"))
      (node (ref "FB1") (pin "1") (pinfunction "1_1") (pintype "passive"))
      (node (ref "U1") (pin "P$9") (pinfunction "VDDA_P$9") (pintype "power_in"))
      (node (ref "U2") (pin "3") (pinfunction "V+_3") (pintype "power_in"))
    )
    (net (code "32") (name "V_LOAD") (class "Default")
      (node (ref "Q2") (pin "3") (pinfunction "S_3") (pintype "passive"))
      (node (ref "R4") (pin "1") (pinfunction "1_1") (pintype "passive"))
      (node (ref "X2") (pin "3") (pinfunction "KL_3") (pintype "passive"))
    )
    (net (code "33") (name "unconnected-(U1-PA1-PadP$11)") (class "Default")
      (node (ref "U1") (pin "P$11") (pinfunction "PA1_P$11") (pintype "bidirectional"))
    )
    (net (code "34") (name "unconnected-(U1-PA7-PadP$17)") (class "Default")
      (node (ref "U1") (pin "P$17") (pinfunction "PA7_P$17") (pintype "bidirectional"))
    )
    (net (code "35") (name "unconnected-(U1-PA8-PadP$29)") (class "Default")
      (node (ref "U1") (pin "P$29") (pinfunction "PA8_P$29") (pintype "bidirectional"))
    )
    (net (code "36") (name "unconnected-(U1-PA12-PadP$33)") (class "Default")
      (node (ref "U1") (pin "P$33") (pinfunction "PA12_P$33") (pintype "bidirectional"))
    )
    (net (code "37") (name "unconnected-(U1-PB1-PadP$19)") (class "Default")
      (node (ref "U1") (pin "P$19") (pinfunction "PB1_P$19") (pintype "bidirectional"))
    )
    (net (code "38") (name "unconnected-(U1-PB2-PadP$20)") (class "Default")
      (node (ref "U1") (pin "P$20") (pinfunction "PB2_P$20") (pintype "bidirectional"))
    )
    (net (code "39") (name "unconnected-(U1-PB5-PadP$41)") (class "Default")
      (node (ref "U1") (pin "P$41") (pinfunction "PB5_P$41") (pintype "bidirectional"))
    )
    (net (code "40") (name "unconnected-(U1-PB6-PadP$42)") (class "Default")
      (node (ref "U1") (pin "P$42") (pinfunction "PB6_P$42") (pintype "bidirectional"))
    )
    (net (code "41") (name "unconnected-(U1-PB7-PadP$43)") (class "Default")
      (node (ref "U1") (pin "P$43") (pinfunction "PB7_P$43") (pintype "bidirectional"))
    )
    (net (code "42") (name "unconnected-(U1-PB8-PadP$45)") (class "Default")
      (node (ref "U1") (pin "P$45") (pinfunction "PB8_P$45") (pintype "bidirectional"))
    )
    (net (code "43") (name "unconnected-(U1-PB9-PadP$46)") (class "Default")
      (node (ref "U1") (pin "P$46") (pinfunction "PB9_P$46") (pintype "bidirectional"))
    )
    (net (code "44") (name "unconnected-(U1-PB12-PadP$25)") (class "Default")
      (node (ref "U1") (pin "P$25") (pinfunction "PB12_P$25") (pintype "bidirectional"))
    )
    (net (code "45") (name "unconnected-(U1-PB13-PadP$26)") (class "Default")
      (node (ref "U1") (pin "P$26") (pinfunction "PB13_P$26") (pintype "bidirectional"))
    )
    (net (code "46") (name "unconnected-(U1-PB15-PadP$28)") (class "Default")
      (node (ref "U1") (pin "P$28") (pinfunction "PB15_P$28") (pintype "bidirectional"))
    )
    (net (code "47") (name "unconnected-(U1-PC14-OSC32_IN-PadP$3)") (class "Default")
      (node (ref "U1") (pin "P$3") (pinfunction "PC14-OSC32_IN_P$3") (pintype "bidirectional"))
    )
    (net (code "48") (name "unconnected-(U1-PC15-OSC32_OUT-PadP$4)") (class "Default")
      (node (ref "U1") (pin "P$4") (pinfunction "PC15-OSC32_OUT_P$4") (pintype "bidirectional"))
    )
  )
)
